# schematic_K3_Tuner.net
KiCad netlist of a schematic drawn in EAGLE
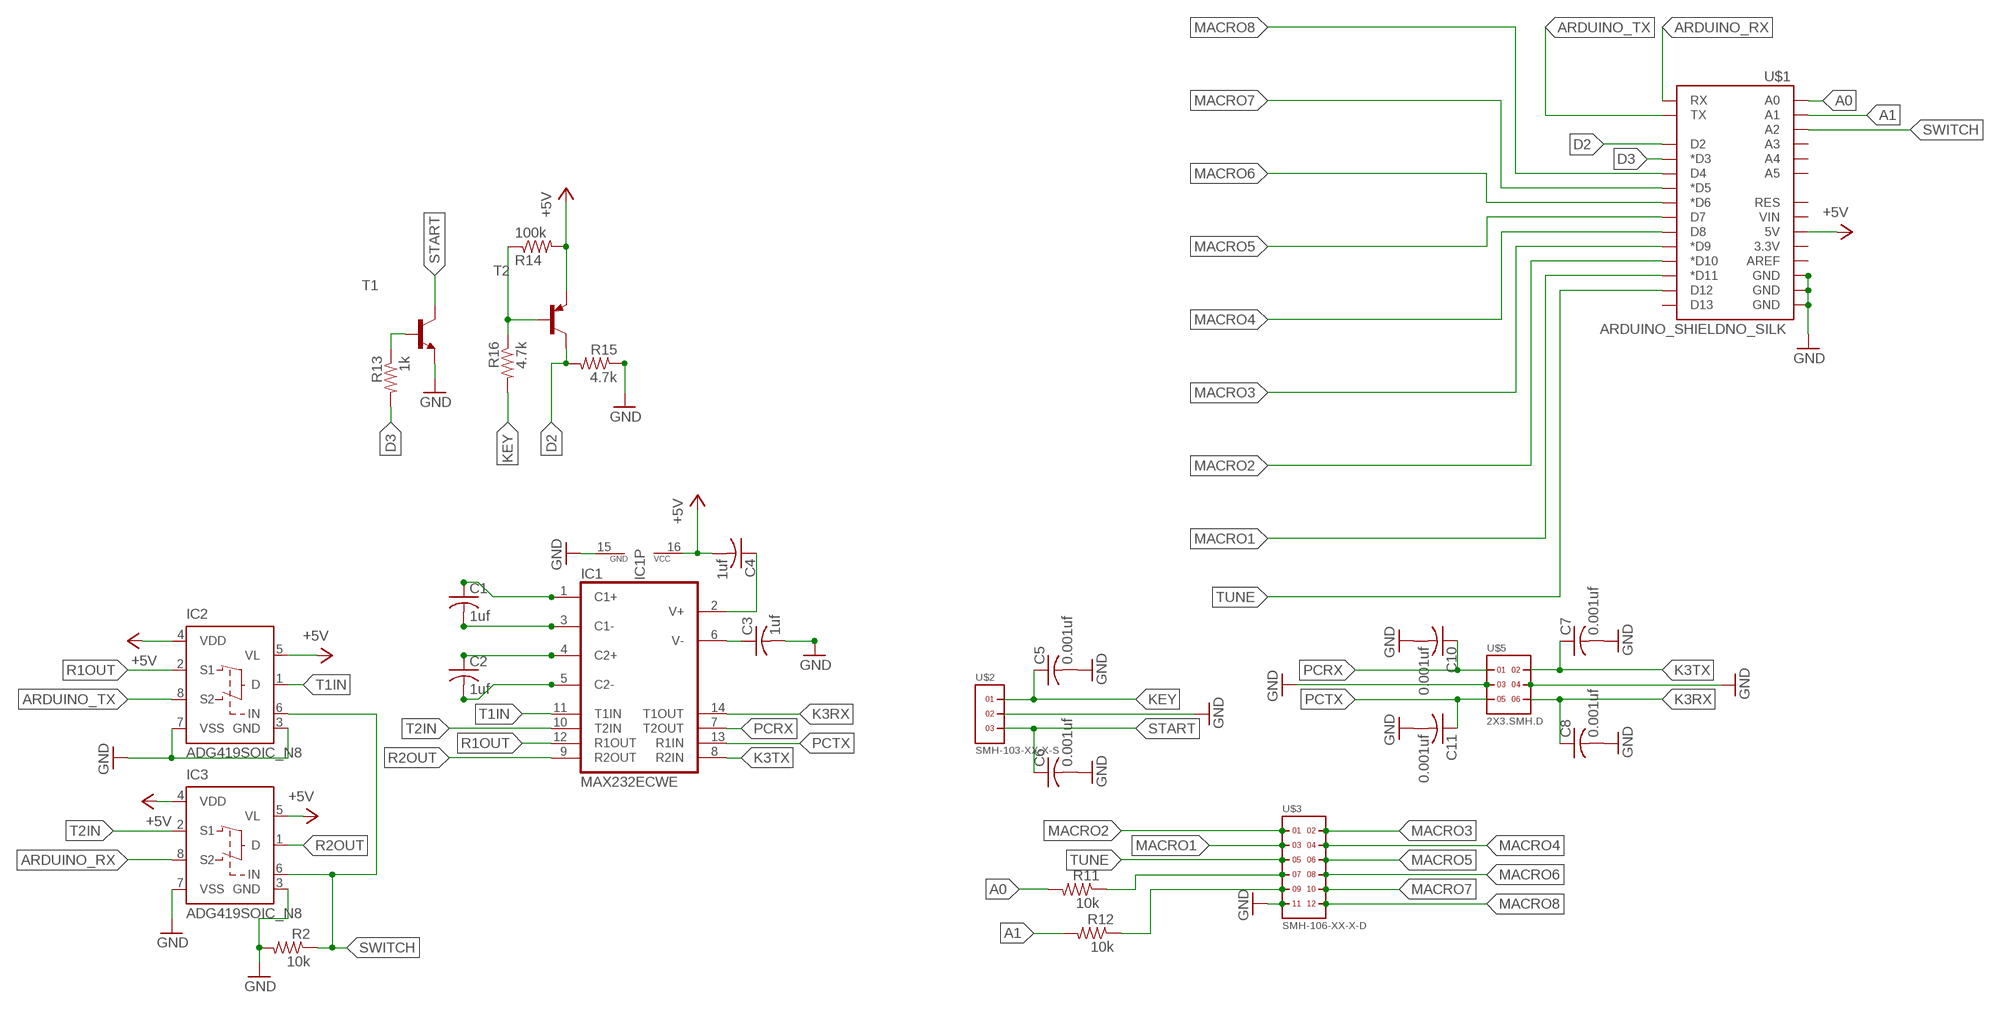
[diagram p0: schematic, sheet 1]

(export (version "E")
  (design (tool "Eeschema 10.0.6"))
  (components
    (comp (ref "C1")
      (value "1uf")
      (footprint "eagle-import:C0805")
      (libsource (lib "eagle-import") (part "C-USC0805"))
    )
    (comp (ref "C2")
      (value "1uf")
      (footprint "eagle-import:C0805")
      (libsource (lib "eagle-import") (part "C-USC0805"))
    )
    (comp (ref "C3")
      (value "1uf")
      (footprint "eagle-import:C0805")
      (libsource (lib "eagle-import") (part "C-USC0805"))
    )
    (comp (ref "C4")
      (value "1uf")
      (footprint "eagle-import:C0805")
      (libsource (lib "eagle-import") (part "C-USC0805"))
    )
    (comp (ref "C5")
      (value "0.001uf")
      (footprint "eagle-import:C0805")
      (libsource (lib "eagle-import") (part "C-USC0805"))
    )
    (comp (ref "C6")
      (value "0.001uf")
      (footprint "eagle-import:C0805")
      (libsource (lib "eagle-import") (part "C-USC0805"))
    )
    (comp (ref "C7")
      (value "0.001uf")
      (footprint "eagle-import:C0805")
      (libsource (lib "eagle-import") (part "C-USC0805"))
    )
    (comp (ref "C8")
      (value "0.001uf")
      (footprint "eagle-import:C0805")
      (libsource (lib "eagle-import") (part "C-USC0805"))
    )
    (comp (ref "C10")
      (value "0.001uf")
      (footprint "eagle-import:C0805")
      (libsource (lib "eagle-import") (part "C-USC0805"))
    )
    (comp (ref "C11")
      (value "0.001uf")
      (footprint "eagle-import:C0805")
      (libsource (lib "eagle-import") (part "C-USC0805"))
    )
    (comp (ref "IC1")
      (value "MAX232ECWE")
      (footprint "eagle-import:SO16L")
      (fields (field (name "MF") "MAXIM") (field (name "MPN") "MAX232ECWE+"))
      (libsource (lib "eagle-import") (part "MAX232ECWE"))
    )
    (comp (ref "IC2")
      (value "ADG419SOIC_N8")
      (footprint "eagle-import:SOIC8")
      (libsource (lib "eagle-import") (part "ADG419SOIC_N8"))
    )
    (comp (ref "IC3")
      (value "ADG419SOIC_N8")
      (footprint "eagle-import:SOIC8")
      (libsource (lib "eagle-import") (part "ADG419SOIC_N8"))
    )
    (comp (ref "R2")
      (value "10k")
      (footprint "eagle-import:M0805")
      (libsource (lib "eagle-import") (part "R-US_M0805"))
    )
    (comp (ref "R11")
      (value "10k")
      (footprint "eagle-import:M0805")
      (libsource (lib "eagle-import") (part "R-US_M0805"))
    )
    (comp (ref "R12")
      (value "10k")
      (footprint "eagle-import:M0805")
      (libsource (lib "eagle-import") (part "R-US_M0805"))
    )
    (comp (ref "R13")
      (value "1k")
      (footprint "eagle-import:M0805")
      (libsource (lib "eagle-import") (part "R-US_M0805"))
    )
    (comp (ref "R14")
      (value "100k")
      (footprint "eagle-import:M0805")
      (libsource (lib "eagle-import") (part "R-US_M0805"))
    )
    (comp (ref "R15")
      (value "4.7k")
      (footprint "eagle-import:M0805")
      (libsource (lib "eagle-import") (part "R-US_M0805"))
    )
    (comp (ref "R16")
      (value "4.7k")
      (footprint "eagle-import:M0805")
      (libsource (lib "eagle-import") (part "R-US_M0805"))
    )
    (comp (ref "T1")
      (value "MMBT3904LT1-NPN-SOT23-BEC")
      (footprint "eagle-import:SOT23-BEC")
      (libsource (lib "eagle-import") (part "-NPN-SOT23-BECMMBT3904LT1"))
    )
    (comp (ref "T2")
      (value "MMBT3906LT1-PNP-SOT23-BEC")
      (footprint "eagle-import:SOT23-BEC")
      (libsource (lib "eagle-import") (part "-PNP-SOT23-BECMMBT3906LT1"))
    )
    (comp (ref "U$1")
      (value "ARDUINO_SHIELDNO_SILK")
      (footprint "eagle-import:DUEMILANOVE_VIAS")
      (libsource (lib "eagle-import") (part "ARDUINO_SHIELDNO_SILK"))
    )
    (comp (ref "U$2")
      (value "SMH-103-XX-X-S")
      (footprint "eagle-import:SMH-103-XX-X-S")
      (libsource (lib "eagle-import") (part "SMH-103-XX-X-S"))
    )
    (comp (ref "U$3")
      (value "SMH-106-XX-X-D")
      (footprint "eagle-import:SMH-106-XX-X-D")
      (libsource (lib "eagle-import") (part "SMH-106-XX-X-D"))
    )
    (comp (ref "U$5")
      (value "2X3.SMH.D")
      (footprint "eagle-import:SMH-103-XX-X-D")
      (libsource (lib "eagle-import") (part "2X3.SMH.D"))
    )
  )
  (nets
    (net (code "1") (name "+5V") (class "Default")
      (node (ref "C4") (pin "2") (pinfunction "2_2") (pintype "passive"))
      (node (ref "IC1") (pin "16") (pinfunction "VCC_16") (pintype "power_in"))
      (node (ref "IC2") (pin "4") (pinfunction "VDD_4") (pintype "power_in"))
      (node (ref "IC2") (pin "5") (pinfunction "VL_5") (pintype "power_in"))
      (node (ref "IC3") (pin "4") (pinfunction "VDD_4") (pintype "power_in"))
      (node (ref "IC3") (pin "5") (pinfunction "VL_5") (pintype "power_in"))
      (node (ref "R14") (pin "2") (pinfunction "2_2") (pintype "passive"))
      (node (ref "T2") (pin "E") (pinfunction "E_E") (pintype "passive"))
      (node (ref "U$1") (pin "5V") (pinfunction "5V_5V") (pintype "bidirectional"))
    )
    (net (code "2") (name "A0") (class "Default")
      (node (ref "R11") (pin "2") (pinfunction "2_2") (pintype "passive"))
      (node (ref "U$1") (pin "A0") (pinfunction "A0_A0") (pintype "bidirectional"))
    )
    (net (code "3") (name "A1") (class "Default")
      (node (ref "R12") (pin "2") (pinfunction "2_2") (pintype "passive"))
      (node (ref "U$1") (pin "A1") (pinfunction "A1_A1") (pintype "bidirectional"))
    )
    (net (code "4") (name "ARDUINO_RX") (class "Default")
      (node (ref "IC3") (pin "8") (pinfunction "S2_8") (pintype "bidirectional"))
      (node (ref "U$1") (pin "RX") (pinfunction "RX_RX") (pintype "bidirectional"))
    )
    (net (code "5") (name "ARDUINO_TX") (class "Default")
      (node (ref "IC2") (pin "8") (pinfunction "S2_8") (pintype "bidirectional"))
      (node (ref "U$1") (pin "TX") (pinfunction "TX_TX") (pintype "bidirectional"))
    )
    (net (code "6") (name "D2") (class "Default")
      (node (ref "R15") (pin "2") (pinfunction "2_2") (pintype "passive"))
      (node (ref "T2") (pin "C") (pinfunction "C_C") (pintype "passive"))
      (node (ref "U$1") (pin "D2") (pinfunction "D2_D2") (pintype "bidirectional"))
    )
    (net (code "7") (name "D3") (class "Default")
      (node (ref "R13") (pin "2") (pinfunction "2_2") (pintype "passive"))
      (node (ref "U$1") (pin "D3") (pinfunction "*D3_D3") (pintype "bidirectional"))
    )
    (net (code "8") (name "GND") (class "Default")
      (node (ref "C10") (pin "2") (pinfunction "2_2") (pintype "passive"))
      (node (ref "C11") (pin "2") (pinfunction "2_2") (pintype "passive"))
      (node (ref "C3") (pin "2") (pinfunction "2_2") (pintype "passive"))
      (node (ref "C5") (pin "2") (pinfunction "2_2") (pintype "passive"))
      (node (ref "C6") (pin "2") (pinfunction "2_2") (pintype "passive"))
      (node (ref "C7") (pin "2") (pinfunction "2_2") (pintype "passive"))
      (node (ref "C8") (pin "2") (pinfunction "2_2") (pintype "passive"))
      (node (ref "IC1") (pin "15") (pinfunction "GND_15") (pintype "power_in"))
      (node (ref "IC2") (pin "3") (pinfunction "GND_3") (pintype "power_in"))
      (node (ref "IC2") (pin "7") (pinfunction "VSS_7") (pintype "power_in"))
      (node (ref "IC3") (pin "3") (pinfunction "GND_3") (pintype "power_in"))
      (node (ref "IC3") (pin "7") (pinfunction "VSS_7") (pintype "power_in"))
      (node (ref "R15") (pin "1") (pinfunction "1_1") (pintype "passive"))
      (node (ref "R2") (pin "2") (pinfunction "2_2") (pintype "passive"))
      (node (ref "T1") (pin "E") (pinfunction "E_E") (pintype "passive"))
      (node (ref "U$1") (pin "GND@0") (pinfunction "GND_GND@0") (pintype "bidirectional"))
      (node (ref "U$1") (pin "GND@1") (pinfunction "GND_GND@1") (pintype "bidirectional"))
      (node (ref "U$1") (pin "GND@2") (pinfunction "GND_GND@2") (pintype "bidirectional"))
      (node (ref "U$2") (pin "2") (pinfunction "2_2") (pintype "bidirectional"))
      (node (ref "U$3") (pin "11") (pinfunction "11_11") (pintype "bidirectional"))
      (node (ref "U$5") (pin "3") (pinfunction "3_3") (pintype "bidirectional"))
      (node (ref "U$5") (pin "4") (pinfunction "4_4") (pintype "bidirectional"))
    )
    (net (code "9") (name "K3RX") (class "Default")
      (node (ref "C8") (pin "1") (pinfunction "1_1") (pintype "passive"))
      (node (ref "IC1") (pin "14") (pinfunction "T1OUT_14") (pintype "output"))
      (node (ref "U$5") (pin "6") (pinfunction "6_6") (pintype "bidirectional"))
    )
    (net (code "10") (name "K3TX") (class "Default")
      (node (ref "C7") (pin "1") (pinfunction "1_1") (pintype "passive"))
      (node (ref "IC1") (pin "8") (pinfunction "R2IN_8") (pintype "input"))
      (node (ref "U$5") (pin "2") (pinfunction "2_2") (pintype "bidirectional"))
    )
    (net (code "11") (name "KEY") (class "Default")
      (node (ref "C5") (pin "1") (pinfunction "1_1") (pintype "passive"))
      (node (ref "R16") (pin "2") (pinfunction "2_2") (pintype "passive"))
      (node (ref "U$2") (pin "1") (pinfunction "1_1") (pintype "bidirectional"))
    )
    (net (code "12") (name "MACRO1") (class "Default")
      (node (ref "U$1") (pin "D11") (pinfunction "*D11_D11") (pintype "bidirectional"))
      (node (ref "U$3") (pin "3") (pinfunction "3_3") (pintype "bidirectional"))
    )
    (net (code "13") (name "MACRO2") (class "Default")
      (node (ref "U$1") (pin "D10") (pinfunction "*D10_D10") (pintype "bidirectional"))
      (node (ref "U$3") (pin "1") (pinfunction "1_1") (pintype "bidirectional"))
    )
    (net (code "14") (name "MACRO3") (class "Default")
      (node (ref "U$1") (pin "D9") (pinfunction "*D9_D9") (pintype "bidirectional"))
      (node (ref "U$3") (pin "2") (pinfunction "2_2") (pintype "bidirectional"))
    )
    (net (code "15") (name "MACRO4") (class "Default")
      (node (ref "U$1") (pin "D8") (pinfunction "D8_D8") (pintype "bidirectional"))
      (node (ref "U$3") (pin "4") (pinfunction "4_4") (pintype "bidirectional"))
    )
    (net (code "16") (name "MACRO5") (class "Default")
      (node (ref "U$1") (pin "D7") (pinfunction "D7_D7") (pintype "bidirectional"))
      (node (ref "U$3") (pin "6") (pinfunction "6_6") (pintype "bidirectional"))
    )
    (net (code "17") (name "MACRO6") (class "Default")
      (node (ref "U$1") (pin "D6") (pinfunction "*D6_D6") (pintype "bidirectional"))
      (node (ref "U$3") (pin "8") (pinfunction "8_8") (pintype "bidirectional"))
    )
    (net (code "18") (name "MACRO7") (class "Default")
      (node (ref "U$1") (pin "D5") (pinfunction "*D5_D5") (pintype "bidirectional"))
      (node (ref "U$3") (pin "10") (pinfunction "10_10") (pintype "bidirectional"))
    )
    (net (code "19") (name "MACRO8") (class "Default")
      (node (ref "U$1") (pin "D4") (pinfunction "D4_D4") (pintype "bidirectional"))
      (node (ref "U$3") (pin "12") (pinfunction "12_12") (pintype "bidirectional"))
    )
    (net (code "20") (name "Net-(IC1A-C1+)") (class "Default")
      (node (ref "C1") (pin "1") (pinfunction "1_1") (pintype "passive"))
      (node (ref "IC1") (pin "1") (pinfunction "C1+_1") (pintype "bidirectional"))
    )
    (net (code "21") (name "Net-(IC1A-C1-)") (class "Default")
      (node (ref "C1") (pin "2") (pinfunction "2_2") (pintype "passive"))
      (node (ref "IC1") (pin "3") (pinfunction "C1-_3") (pintype "bidirectional"))
    )
    (net (code "22") (name "Net-(IC1A-C2+)") (class "Default")
      (node (ref "C2") (pin "1") (pinfunction "1_1") (pintype "passive"))
      (node (ref "IC1") (pin "4") (pinfunction "C2+_4") (pintype "bidirectional"))
    )
    (net (code "23") (name "Net-(IC1A-C2-)") (class "Default")
      (node (ref "C2") (pin "2") (pinfunction "2_2") (pintype "passive"))
      (node (ref "IC1") (pin "5") (pinfunction "C2-_5") (pintype "bidirectional"))
    )
    (net (code "24") (name "Net-(IC1A-V+)") (class "Default")
      (node (ref "C4") (pin "1") (pinfunction "1_1") (pintype "passive"))
      (node (ref "IC1") (pin "2") (pinfunction "V+_2") (pintype "bidirectional"))
    )
    (net (code "25") (name "Net-(IC1A-V-)") (class "Default")
      (node (ref "C3") (pin "1") (pinfunction "1_1") (pintype "passive"))
      (node (ref "IC1") (pin "6") (pinfunction "V-_6") (pintype "bidirectional"))
    )
    (net (code "26") (name "Net-(R11-Pad1)") (class "Default")
      (node (ref "R11") (pin "1") (pinfunction "1_1") (pintype "passive"))
      (node (ref "U$3") (pin "7") (pinfunction "7_7") (pintype "bidirectional"))
    )
    (net (code "27") (name "Net-(R12-Pad1)") (class "Default")
      (node (ref "R12") (pin "1") (pinfunction "1_1") (pintype "passive"))
      (node (ref "U$3") (pin "9") (pinfunction "9_9") (pintype "bidirectional"))
    )
    (net (code "28") (name "Net-(R13-Pad1)") (class "Default")
      (node (ref "R13") (pin "1") (pinfunction "1_1") (pintype "passive"))
      (node (ref "T1") (pin "B") (pinfunction "B_B") (pintype "passive"))
    )
    (net (code "29") (name "Net-(R14-Pad1)") (class "Default")
      (node (ref "R14") (pin "1") (pinfunction "1_1") (pintype "passive"))
      (node (ref "R16") (pin "1") (pinfunction "1_1") (pintype "passive"))
      (node (ref "T2") (pin "B") (pinfunction "B_B") (pintype "passive"))
    )
    (net (code "30") (name "PCRX") (class "Default")
      (node (ref "C10") (pin "1") (pinfunction "1_1") (pintype "passive"))
      (node (ref "IC1") (pin "7") (pinfunction "T2OUT_7") (pintype "output"))
      (node (ref "U$5") (pin "1") (pinfunction "1_1") (pintype "bidirectional"))
    )
    (net (code "31") (name "PCTX") (class "Default")
      (node (ref "C11") (pin "1") (pinfunction "1_1") (pintype "passive"))
      (node (ref "IC1") (pin "13") (pinfunction "R1IN_13") (pintype "input"))
      (node (ref "U$5") (pin "5") (pinfunction "5_5") (pintype "bidirectional"))
    )
    (net (code "32") (name "R1OUT") (class "Default")
      (node (ref "IC1") (pin "12") (pinfunction "R1OUT_12") (pintype "output"))
      (node (ref "IC2") (pin "2") (pinfunction "S1_2") (pintype "bidirectional"))
    )
    (net (code "33") (name "R2OUT") (class "Default")
      (node (ref "IC1") (pin "9") (pinfunction "R2OUT_9") (pintype "output"))
      (node (ref "IC3") (pin "1") (pinfunction "D_1") (pintype "bidirectional"))
    )
    (net (code "34") (name "START") (class "Default")
      (node (ref "C6") (pin "1") (pinfunction "1_1") (pintype "passive"))
      (node (ref "T1") (pin "C") (pinfunction "C_C") (pintype "passive"))
      (node (ref "U$2") (pin "3") (pinfunction "3_3") (pintype "bidirectional"))
    )
    (net (code "35") (name "SWITCH") (class "Default")
      (node (ref "IC2") (pin "6") (pinfunction "IN_6") (pintype "input"))
      (node (ref "IC3") (pin "6") (pinfunction "IN_6") (pintype "input"))
      (node (ref "R2") (pin "1") (pinfunction "1_1") (pintype "passive"))
      (node (ref "U$1") (pin "A2") (pinfunction "A2_A2") (pintype "bidirectional"))
    )
    (net (code "36") (name "T1IN") (class "Default")
      (node (ref "IC1") (pin "11") (pinfunction "T1IN_11") (pintype "input"))
      (node (ref "IC2") (pin "1") (pinfunction "D_1") (pintype "bidirectional"))
    )
    (net (code "37") (name "T2IN") (class "Default")
      (node (ref "IC1") (pin "10") (pinfunction "T2IN_10") (pintype "input"))
      (node (ref "IC3") (pin "2") (pinfunction "S1_2") (pintype "bidirectional"))
    )
    (net (code "38") (name "TUNE") (class "Default")
      (node (ref "U$1") (pin "D12") (pinfunction "D12_D12") (pintype "bidirectional"))
      (node (ref "U$3") (pin "5") (pinfunction "5_5") (pintype "bidirectional"))
    )
    (net (code "39") (name "unconnected-(U$1-Pad3.3V)") (class "Default")
      (node (ref "U$1") (pin "3.3V") (pinfunction "3.3V_3.3V") (pintype "bidirectional"))
    )
    (net (code "40") (name "unconnected-(U$1-PadA3)") (class "Default")
      (node (ref "U$1") (pin "A3") (pinfunction "A3_A3") (pintype "bidirectional"))
    )
    (net (code "41") (name "unconnected-(U$1-PadA4)") (class "Default")
      (node (ref "U$1") (pin "A4") (pinfunction "A4_A4") (pintype "bidirectional"))
    )
    (net (code "42") (name "unconnected-(U$1-PadA5)") (class "Default")
      (node (ref "U$1") (pin "A5") (pinfunction "A5_A5") (pintype "bidirectional"))
    )
    (net (code "43") (name "unconnected-(U$1-PadAREF)") (class "Default")
      (node (ref "U$1") (pin "AREF") (pinfunction "AREF_AREF") (pintype "bidirectional"))
    )
    (net (code "44") (name "unconnected-(U$1-PadD13)") (class "Default")
      (node (ref "U$1") (pin "D13") (pinfunction "D13_D13") (pintype "bidirectional"))
    )
    (net (code "45") (name "unconnected-(U$1-PadRES)") (class "Default")
      (node (ref "U$1") (pin "RES") (pinfunction "RES_RES") (pintype "bidirectional"))
    )
    (net (code "46") (name "unconnected-(U$1-PadVIN)") (class "Default")
      (node (ref "U$1") (pin "VIN") (pinfunction "VIN_VIN") (pintype "bidirectional"))
    )
  )
)
